# SCH_Affordable-Quality-Slime-Project-_AQ.net
KiCad netlist of a schematic drawn in EasyEDA
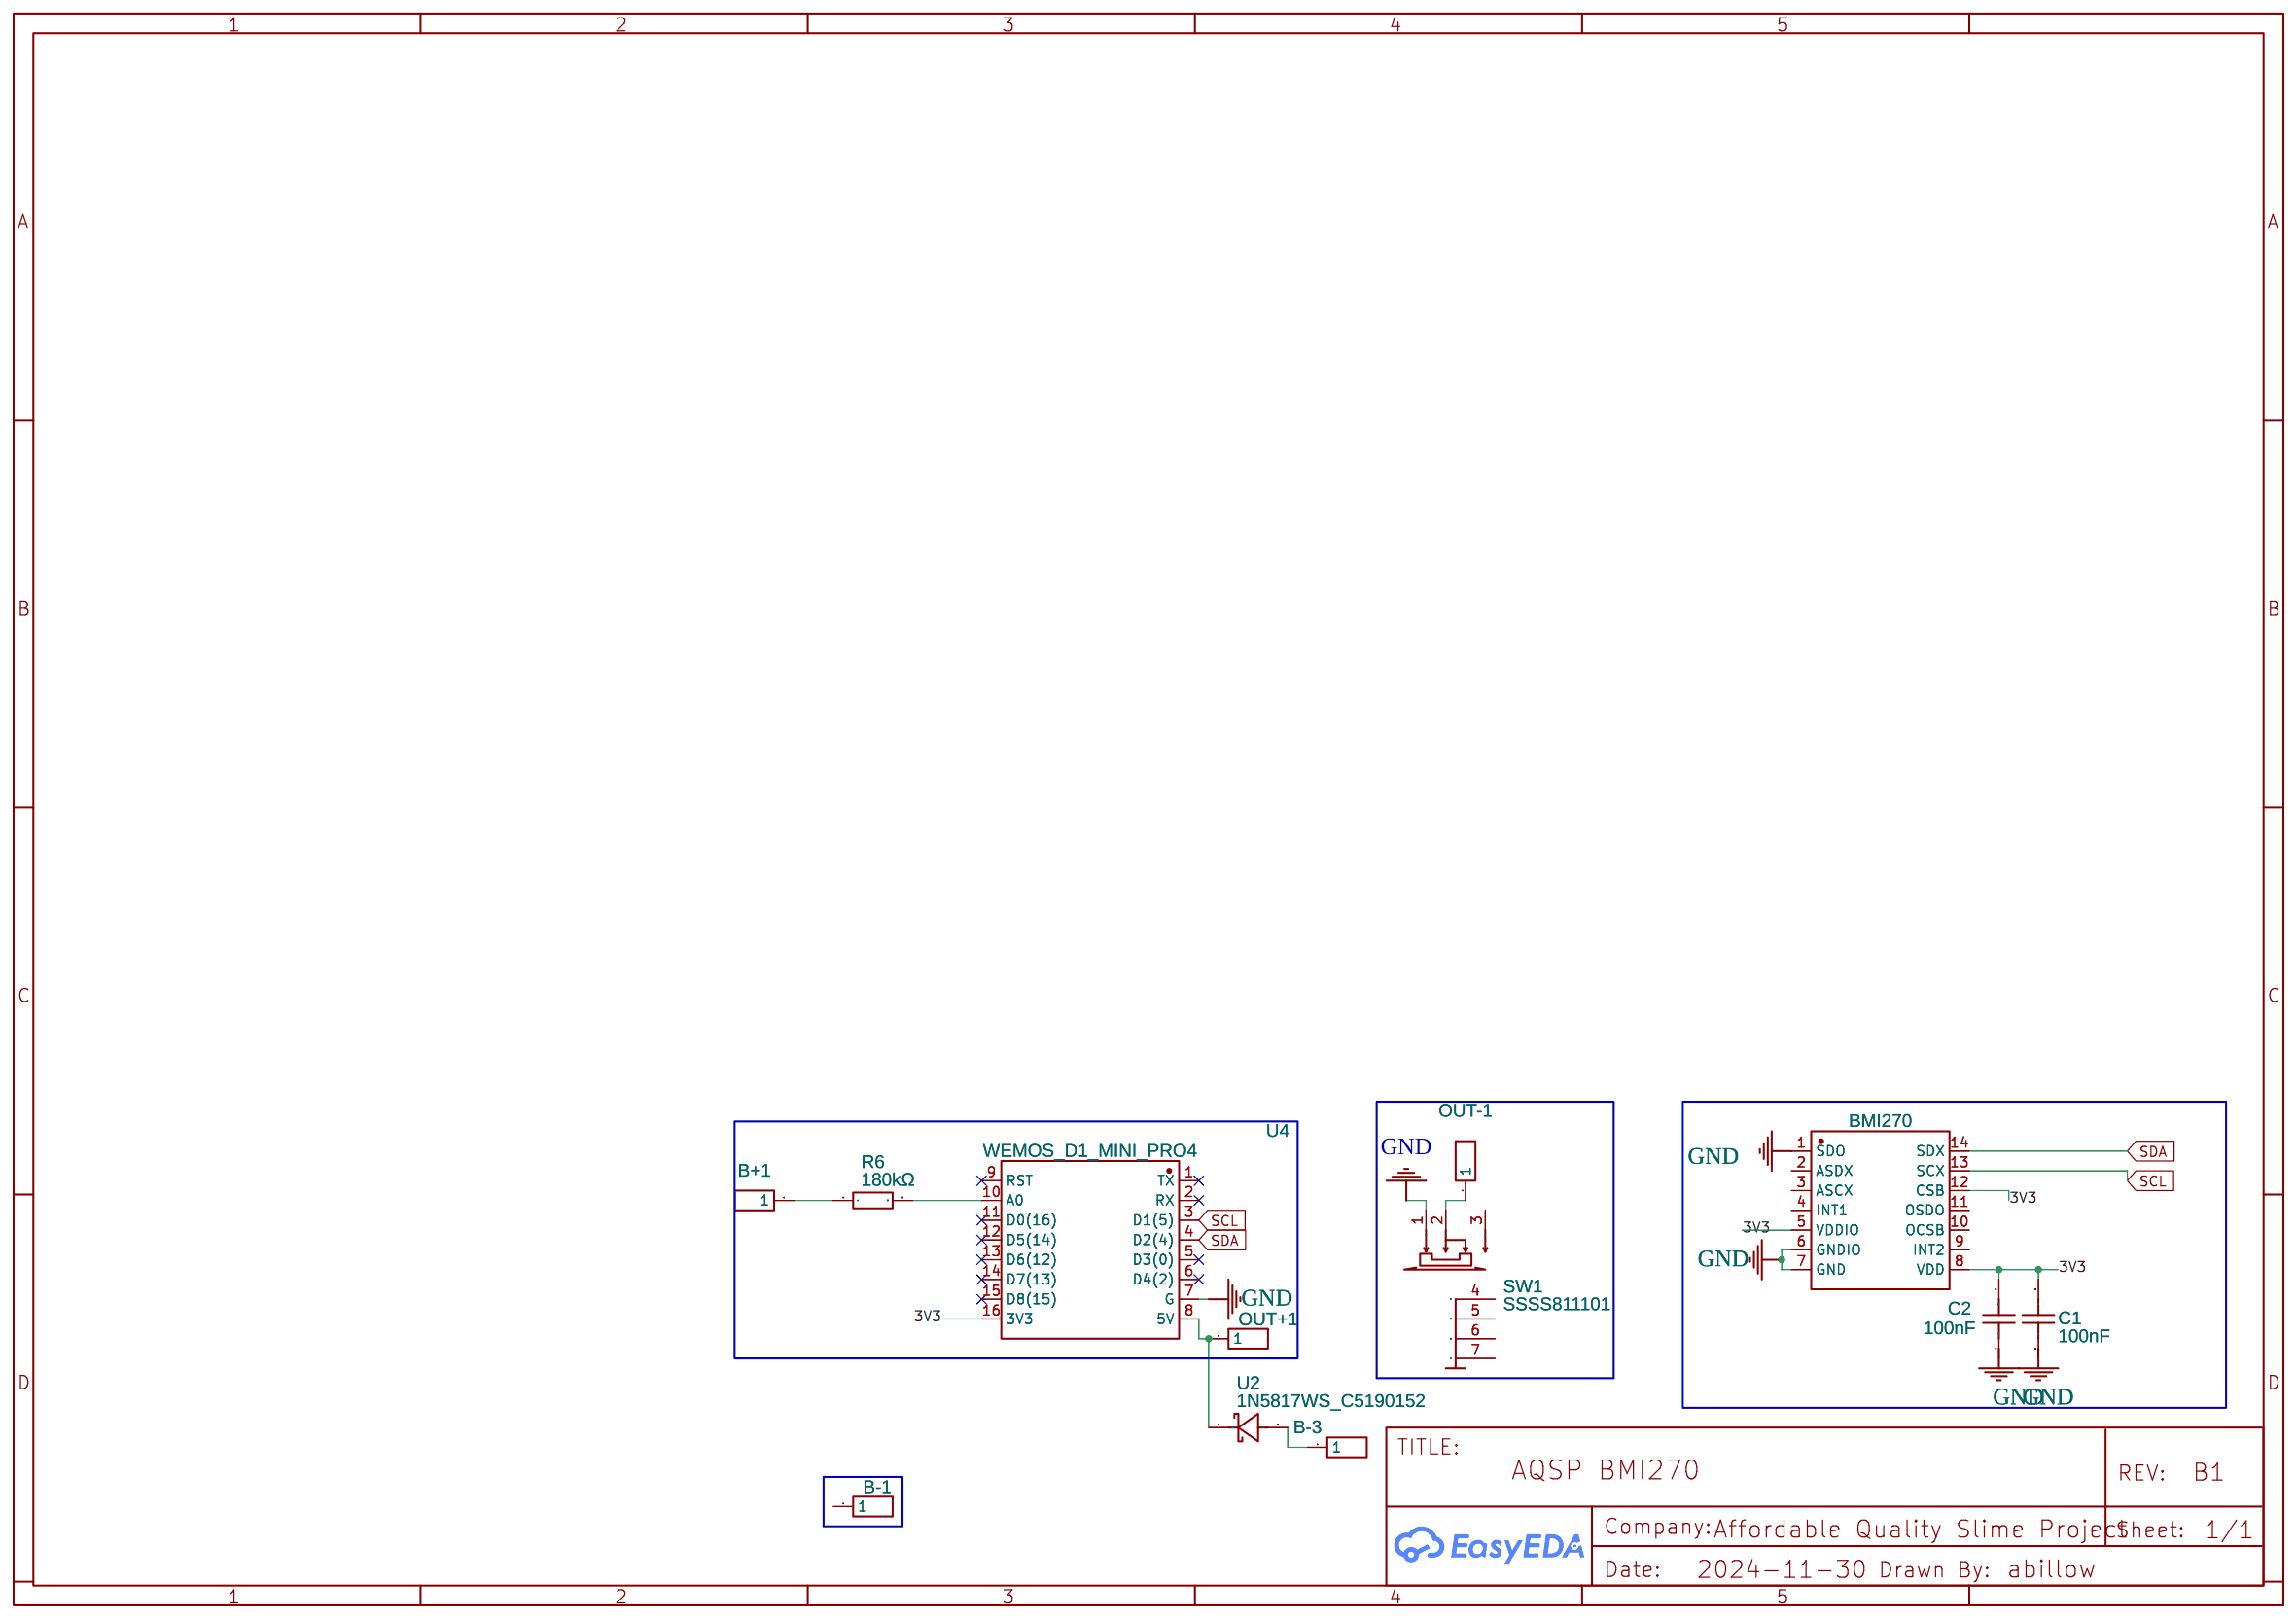
[diagram p0: schematic sheet]

(export (version "E")
  (design (tool "Eeschema 10.0.6"))
  (components
    (comp (ref "B+1")
      (value "Header-Male-2.54_1x1")
      (fields (field (name "Manufacturer") "ReliaPro"))
      (libsource (lib "") (part "Unknown_380_-205"))
    )
    (comp (ref "B-1")
      (value "Header-Male-2.54_1x1")
      (fields (field (name "Manufacturer") "ReliaPro"))
      (libsource (lib "") (part "Unknown_430_-50"))
    )
    (comp (ref "B-3")
      (value "Header-Male-2.54_1x1")
      (fields (field (name "Manufacturer") "ReliaPro"))
      (libsource (lib "") (part "Unknown_670_-80"))
    )
    (comp (ref "C1")
      (value "100nF")
      (fields (field (name "Manufacturer Part") "FN15X104K500PKG") (field (name "Manufacturer") "PSA(信昌电陶)"))
      (libsource (lib "") (part "FN15X104K500PKG"))
    )
    (comp (ref "C2")
      (value "100nF")
      (fields (field (name "Manufacturer Part") "FN15X104K500PKG") (field (name "Manufacturer") "PSA(信昌电陶)"))
      (libsource (lib "") (part "FN15X104K500PKG"))
    )
    (comp (ref "OUT+1")
      (value "Header-Male-2.54_1x1")
      (fields (field (name "Manufacturer") "ReliaPro"))
      (libsource (lib "") (part "Unknown_620_-135"))
    )
    (comp (ref "OUT-1")
      (value "Header-Male-2.54_1x1")
      (fields (field (name "Manufacturer") "ReliaPro"))
      (libsource (lib "") (part "Unknown_735_-220"))
    )
    (comp (ref "R6")
      (value "180kΩ")
      (fields
        (field (name "Manufacturer Part") "MF1/4W-180KΩ±1% T")
        (field (name "Manufacturer") "CCO(千志电子)")
      )
      (libsource (lib "") (part "MF1/4W-180KΩ±1% T52"))
    )
    (comp (ref "SW1")
      (value "SSSS811101")
      (fields (field (name "Manufacturer") "ALPSALPINE(阿尔卑斯阿尔派)"))
      (libsource (lib "") (part "SSSS811101"))
    )
    (comp (ref "U1")
      (value "BMI270")
      (fields (field (name "Manufacturer") "Bosch(博世)"))
      (libsource (lib "") (part "BMI270"))
    )
    (comp (ref "U2")
      (value "1N5817WS_C5190152")
      (fields (field (name "Manufacturer Part") "1N5817WS") (field (name "Manufacturer") "Hottech(合科泰)"))
      (libsource (lib "") (part "1N5817WS_C5190152"))
    )
    (comp (ref "U4")
      (value "WEMOS_D1_MINI_PRO4")
      (fields (field (name "Manufacturer Part") "Wemos_D1_mini_Pro4"))
      (libsource (lib "") (part "WEMOS_D1_MINI_PRO4"))
    )
  )
  (nets
    (net (code "1") (name "/3V3") (class "Default")
      (node (ref "C1") (pin "2") (pinfunction "2_2") (pintype "unspecified"))
      (node (ref "C2") (pin "2") (pinfunction "2_2") (pintype "unspecified"))
      (node (ref "U1") (pin "12") (pinfunction "CSB_12") (pintype "unspecified"))
      (node (ref "U1") (pin "5") (pinfunction "VDDIO_5") (pintype "unspecified"))
      (node (ref "U1") (pin "8") (pinfunction "VDD_8") (pintype "unspecified"))
      (node (ref "U4") (pin "16") (pinfunction "3V3_16") (pintype "unspecified"))
    )
    (net (code "2") (name "GND") (class "Default")
      (node (ref "C1") (pin "1") (pinfunction "1_1") (pintype "unspecified"))
      (node (ref "C2") (pin "1") (pinfunction "1_1") (pintype "unspecified"))
      (node (ref "SW1") (pin "1") (pinfunction "1_1") (pintype "unspecified"))
      (node (ref "U1") (pin "1") (pinfunction "SDO_1") (pintype "unspecified"))
      (node (ref "U1") (pin "6") (pinfunction "GNDIO_6") (pintype "unspecified"))
      (node (ref "U1") (pin "7") (pinfunction "GND_7") (pintype "unspecified"))
      (node (ref "U4") (pin "7") (pinfunction "G_7") (pintype "unspecified"))
    )
    (net (code "3") (name "Net-(B+1-Pad1)") (class "Default")
      (node (ref "B+1") (pin "1") (pinfunction "1_1") (pintype "input"))
      (node (ref "R6") (pin "1") (pinfunction "1_1") (pintype "unspecified"))
    )
    (net (code "4") (name "Net-(OUT-1-Pad1)") (class "Default")
      (node (ref "OUT-1") (pin "1") (pinfunction "1_1") (pintype "input"))
      (node (ref "SW1") (pin "2") (pinfunction "2_2") (pintype "unspecified"))
    )
    (net (code "5") (name "Net-(U2-A)") (class "Default")
      (node (ref "B-3") (pin "1") (pinfunction "1_1") (pintype "input"))
      (node (ref "U2") (pin "2") (pinfunction "A_2") (pintype "unspecified"))
    )
    (net (code "6") (name "Net-(U2-C)") (class "Default")
      (node (ref "OUT+1") (pin "1") (pinfunction "1_1") (pintype "input"))
      (node (ref "U2") (pin "1") (pinfunction "C_1") (pintype "unspecified"))
      (node (ref "U4") (pin "8") (pinfunction "5V_8") (pintype "unspecified"))
    )
    (net (code "7") (name "Net-(U4-A0)") (class "Default")
      (node (ref "R6") (pin "2") (pinfunction "2_2") (pintype "unspecified"))
      (node (ref "U4") (pin "10") (pinfunction "A0_10") (pintype "unspecified"))
    )
    (net (code "8") (name "SCL") (class "Default")
      (node (ref "U1") (pin "13") (pinfunction "SCX_13") (pintype "unspecified"))
      (node (ref "U4") (pin "3") (pinfunction "D1(5)_3") (pintype "unspecified"))
    )
    (net (code "9") (name "SDA") (class "Default")
      (node (ref "U1") (pin "14") (pinfunction "SDX_14") (pintype "unspecified"))
      (node (ref "U4") (pin "4") (pinfunction "D2(4)_4") (pintype "unspecified"))
    )
    (net (code "10") (name "unconnected-(B-1-Pad1)") (class "Default")
      (node (ref "B-1") (pin "1") (pinfunction "1_1") (pintype "input"))
    )
    (net (code "11") (name "unconnected-(SW1-Pad3)") (class "Default")
      (node (ref "SW1") (pin "3") (pinfunction "3_3") (pintype "unspecified"))
    )
    (net (code "12") (name "unconnected-(SW1-Pad4)") (class "Default")
      (node (ref "SW1") (pin "4") (pinfunction "4_4") (pintype "unspecified"))
    )
    (net (code "13") (name "unconnected-(SW1-Pad5)") (class "Default")
      (node (ref "SW1") (pin "5") (pinfunction "5_5") (pintype "unspecified"))
    )
    (net (code "14") (name "unconnected-(SW1-Pad6)") (class "Default")
      (node (ref "SW1") (pin "6") (pinfunction "6_6") (pintype "unspecified"))
    )
    (net (code "15") (name "unconnected-(SW1-Pad7)") (class "Default")
      (node (ref "SW1") (pin "7") (pinfunction "7_7") (pintype "unspecified"))
    )
    (net (code "16") (name "unconnected-(U1-ASCX-Pad3)") (class "Default")
      (node (ref "U1") (pin "3") (pinfunction "ASCX_3") (pintype "unspecified"))
    )
    (net (code "17") (name "unconnected-(U1-ASDX-Pad2)") (class "Default")
      (node (ref "U1") (pin "2") (pinfunction "ASDX_2") (pintype "unspecified"))
    )
    (net (code "18") (name "unconnected-(U1-INT1-Pad4)") (class "Default")
      (node (ref "U1") (pin "4") (pinfunction "INT1_4") (pintype "unspecified"))
    )
    (net (code "19") (name "unconnected-(U1-INT2-Pad9)") (class "Default")
      (node (ref "U1") (pin "9") (pinfunction "INT2_9") (pintype "unspecified"))
    )
    (net (code "20") (name "unconnected-(U1-OCSB-Pad10)") (class "Default")
      (node (ref "U1") (pin "10") (pinfunction "OCSB_10") (pintype "unspecified"))
    )
    (net (code "21") (name "unconnected-(U1-OSDO-Pad11)") (class "Default")
      (node (ref "U1") (pin "11") (pinfunction "OSDO_11") (pintype "unspecified"))
    )
    (net (code "22") (name "unconnected-(U4-D0(16)-Pad11)") (class "Default")
      (node (ref "U4") (pin "11") (pinfunction "D0(16)_11") (pintype "unspecified+no_connect"))
    )
    (net (code "23") (name "unconnected-(U4-D3(0)-Pad5)") (class "Default")
      (node (ref "U4") (pin "5") (pinfunction "D3(0)_5") (pintype "unspecified+no_connect"))
    )
    (net (code "24") (name "unconnected-(U4-D4(2)-Pad6)") (class "Default")
      (node (ref "U4") (pin "6") (pinfunction "D4(2)_6") (pintype "unspecified+no_connect"))
    )
    (net (code "25") (name "unconnected-(U4-D5(14)-Pad12)") (class "Default")
      (node (ref "U4") (pin "12") (pinfunction "D5(14)_12") (pintype "unspecified+no_connect"))
    )
    (net (code "26") (name "unconnected-(U4-D6(12)-Pad13)") (class "Default")
      (node (ref "U4") (pin "13") (pinfunction "D6(12)_13") (pintype "unspecified+no_connect"))
    )
    (net (code "27") (name "unconnected-(U4-D7(13)-Pad14)") (class "Default")
      (node (ref "U4") (pin "14") (pinfunction "D7(13)_14") (pintype "unspecified+no_connect"))
    )
    (net (code "28") (name "unconnected-(U4-D8(15)-Pad15)") (class "Default")
      (node (ref "U4") (pin "15") (pinfunction "D8(15)_15") (pintype "unspecified+no_connect"))
    )
    (net (code "29") (name "unconnected-(U4-RST-Pad9)") (class "Default")
      (node (ref "U4") (pin "9") (pinfunction "RST_9") (pintype "unspecified+no_connect"))
    )
    (net (code "30") (name "unconnected-(U4-RX-Pad2)") (class "Default")
      (node (ref "U4") (pin "2") (pinfunction "RX_2") (pintype "unspecified+no_connect"))
    )
    (net (code "31") (name "unconnected-(U4-TX-Pad1)") (class "Default")
      (node (ref "U4") (pin "1") (pinfunction "TX_1") (pintype "unspecified+no_connect"))
    )
  )
)
